# H04.net
KiCad netlist of a schematic drawn in EAGLE
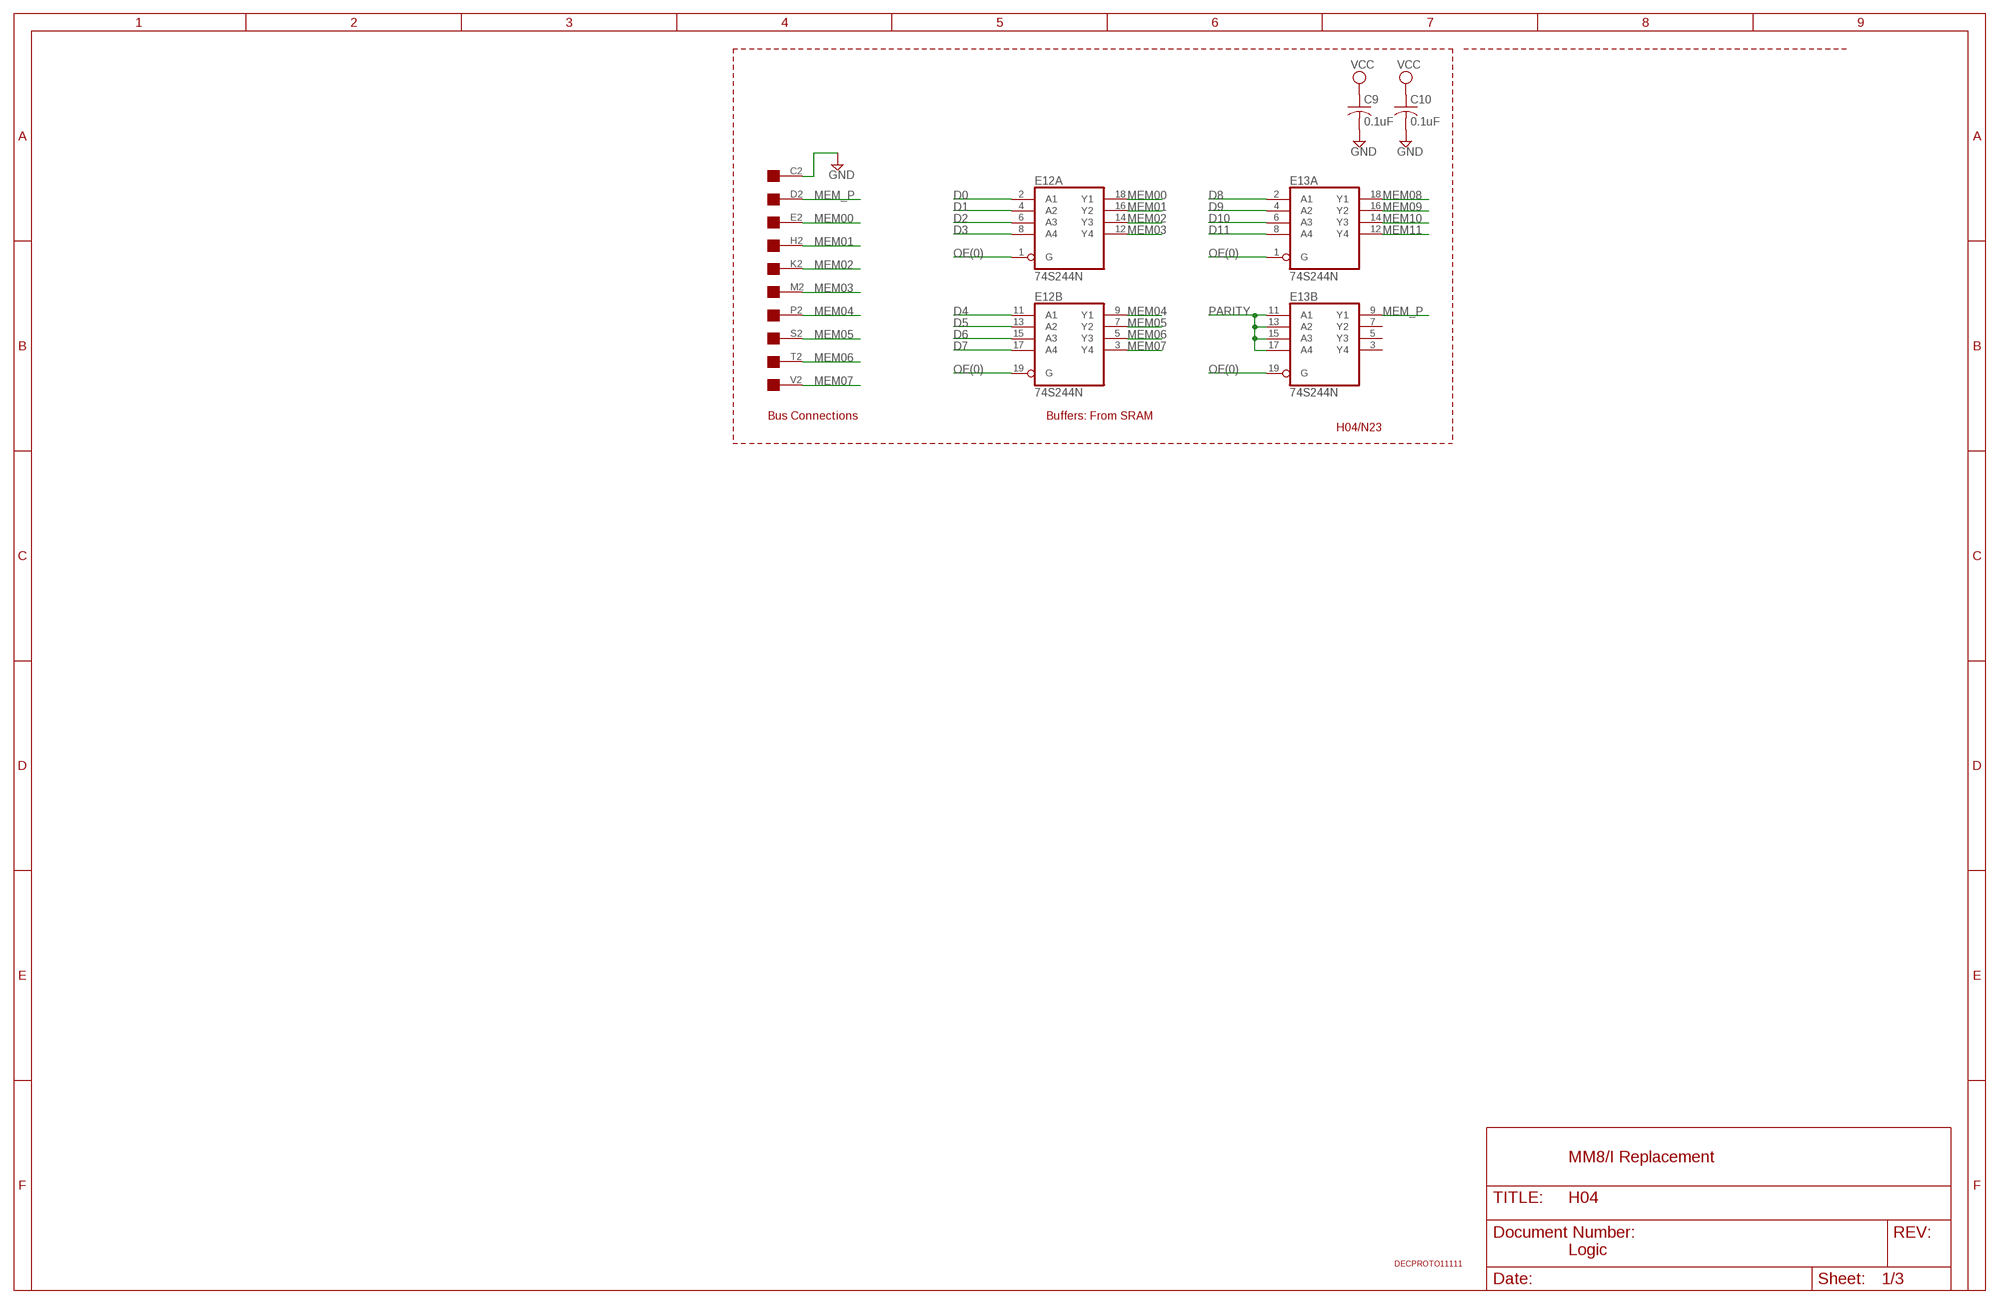
[diagram p0: schematic, sheet 1]
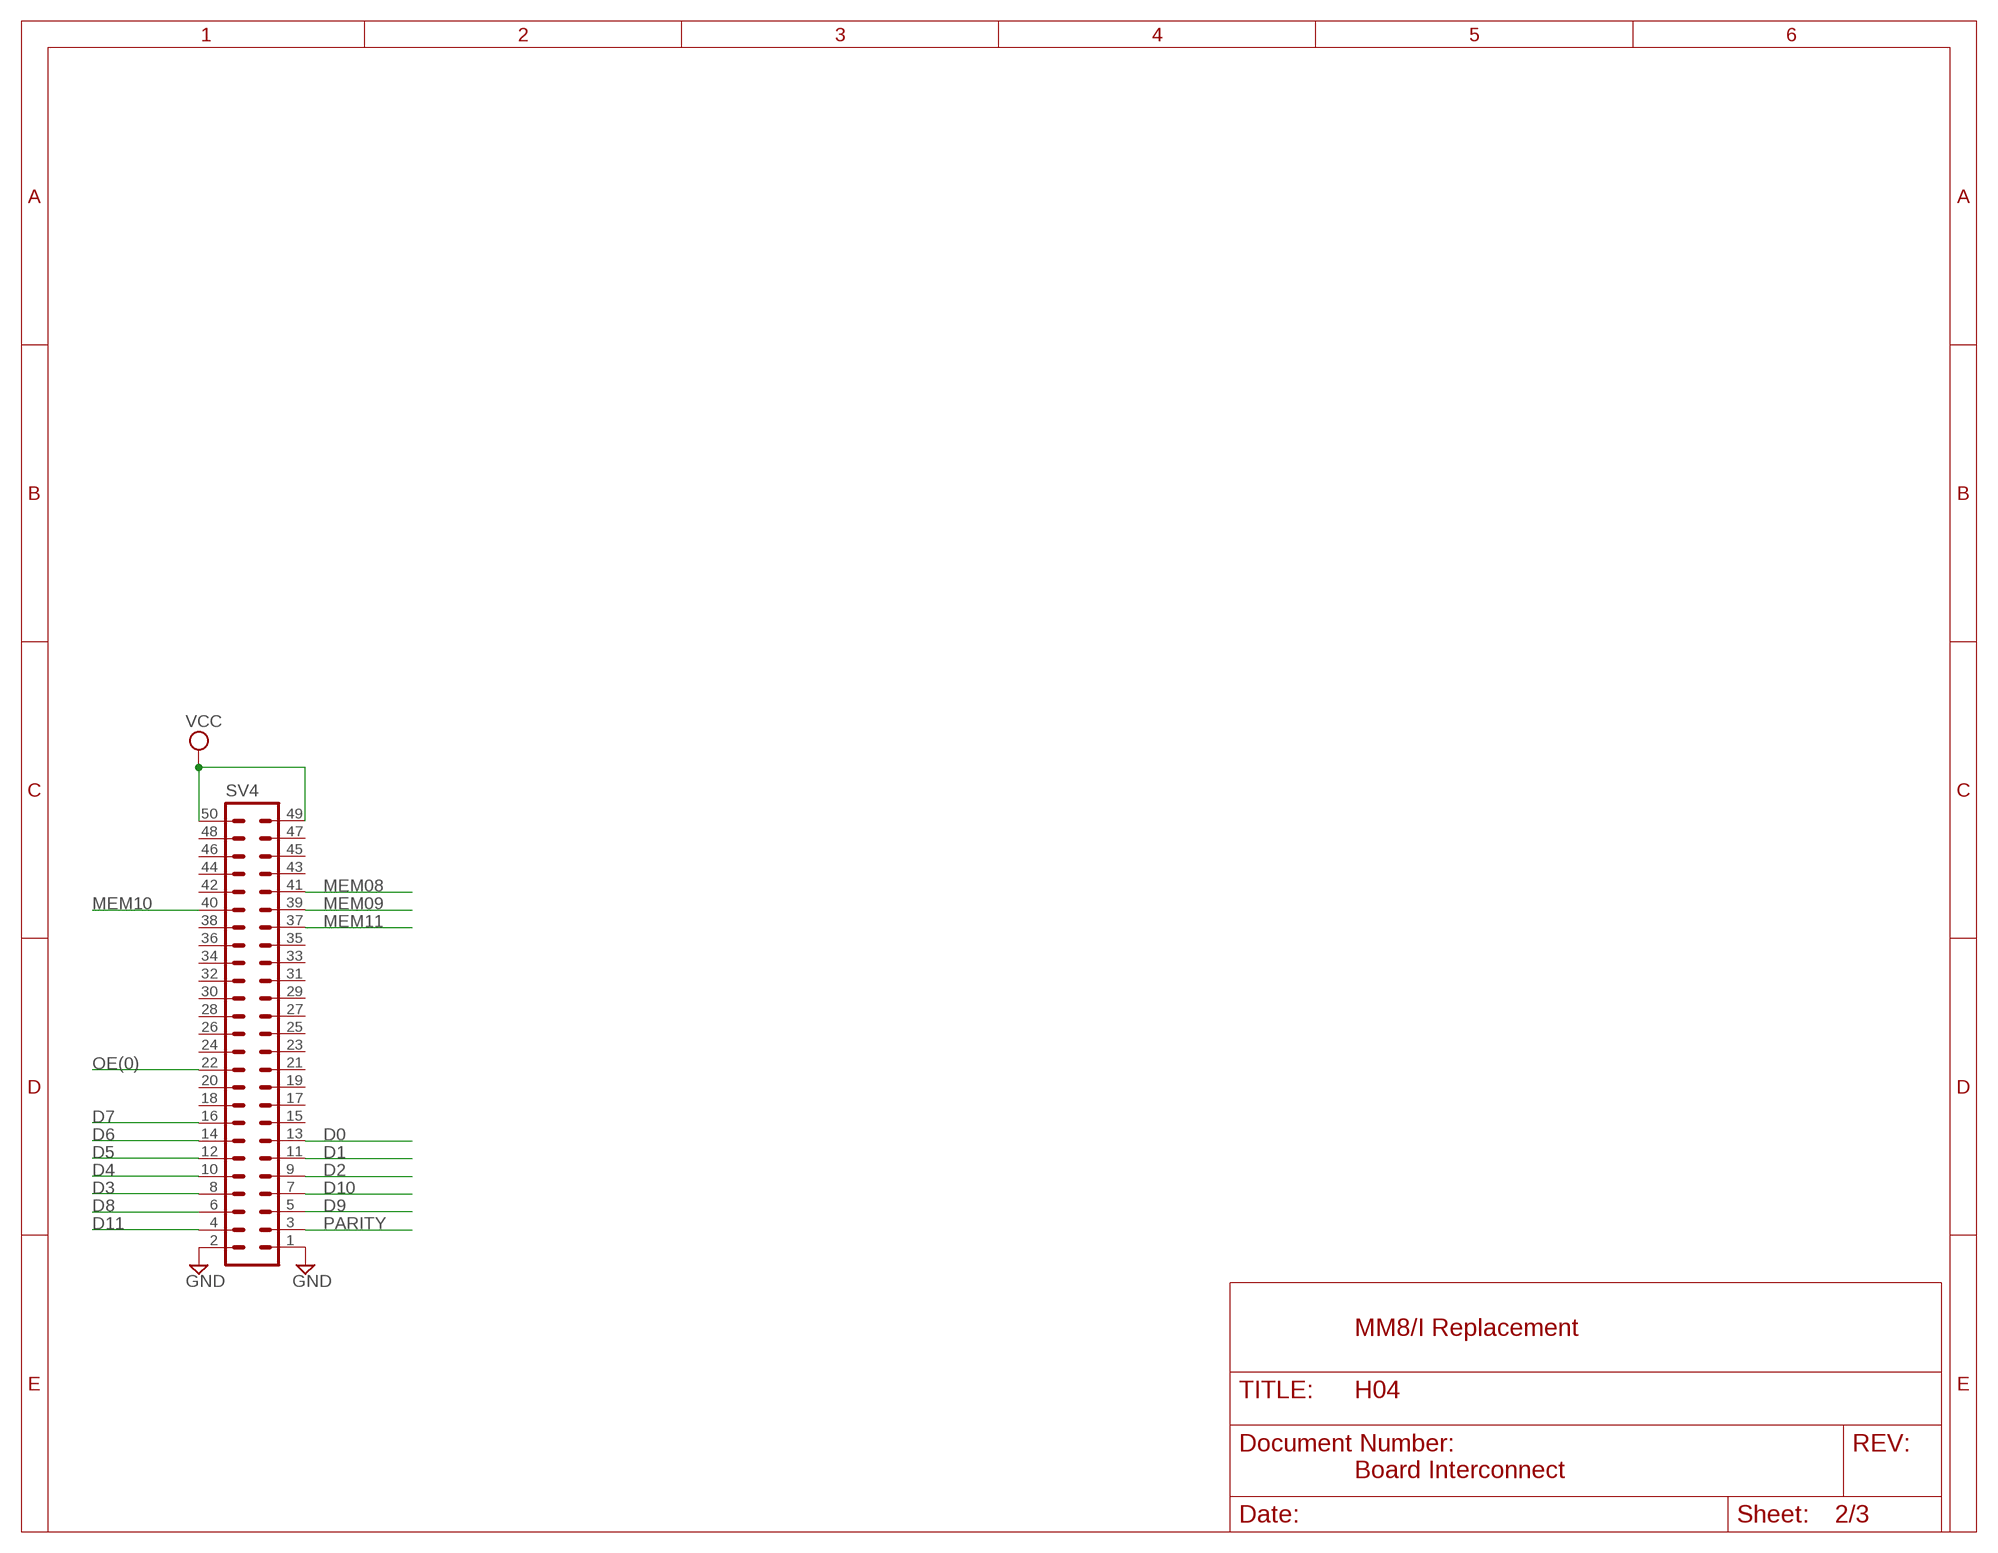
[diagram p1: schematic, sheet 2]
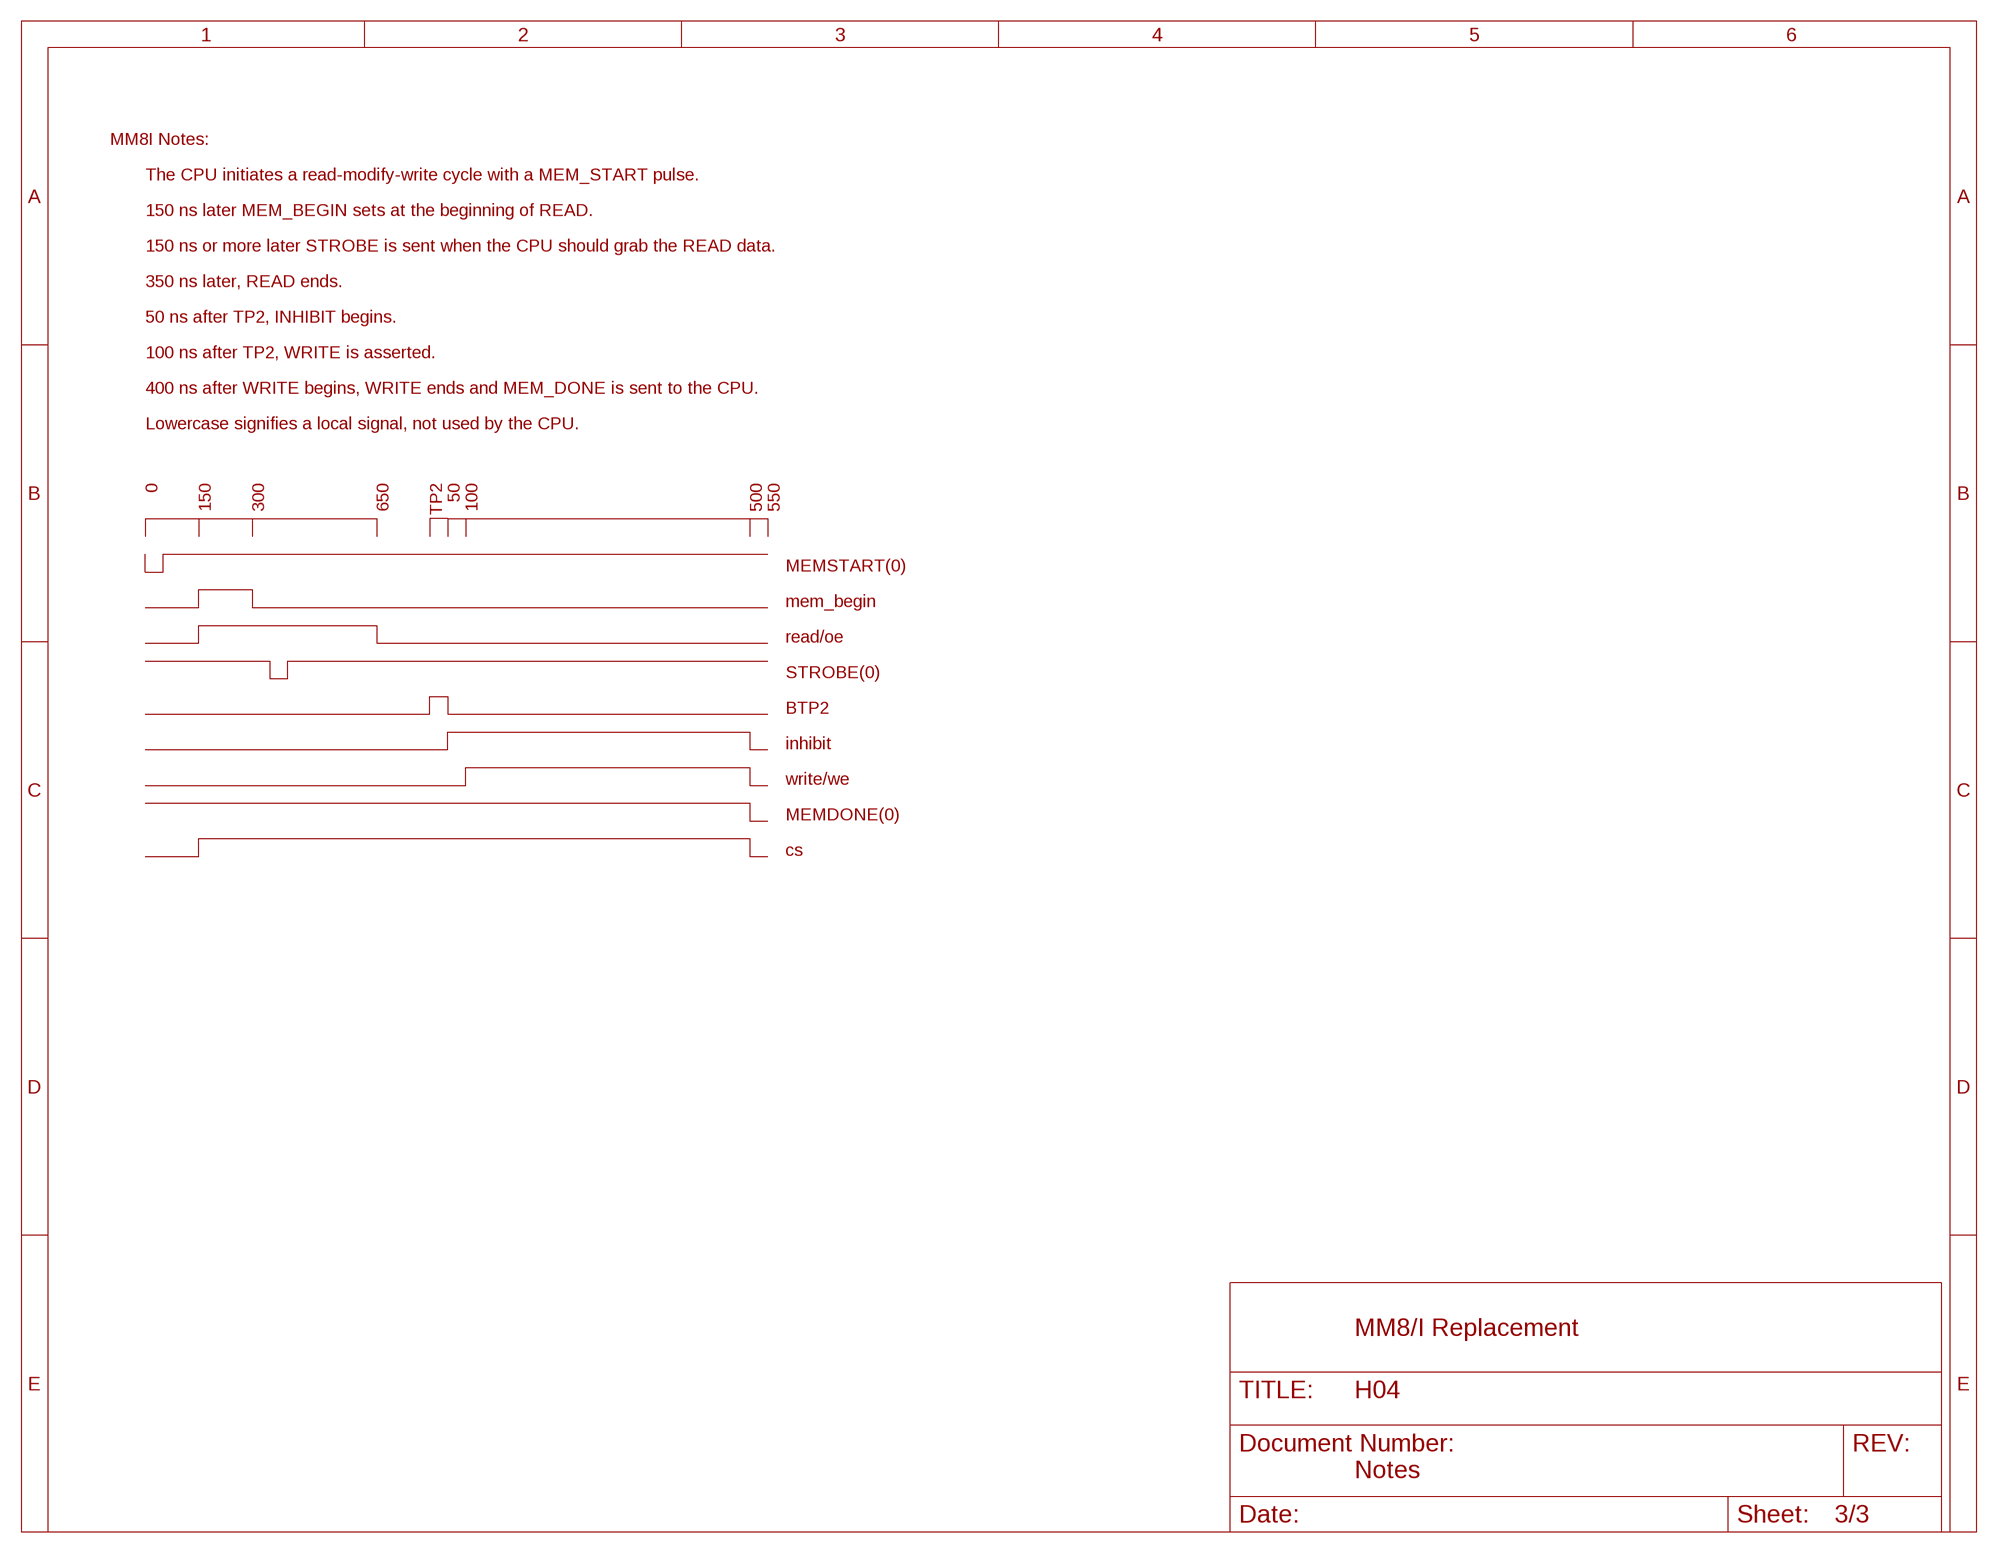
[diagram p2: schematic, sheet 3]

(export (version "E")
  (design (tool "Eeschema 10.0.6"))
  (components
    (comp (ref "SV4")
      (value "ML50L")
      (footprint "eagle-import:ML50L")
      (libsource (lib "eagle-import") (part "ML50L"))
    )
    (comp (ref "C9")
      (value "0.1uF")
      (footprint "eagle-import:C050-025X075")
      (libsource (lib "eagle-import") (part "C-US050-025X075"))
    )
    (comp (ref "C10")
      (value "0.1uF")
      (footprint "eagle-import:C050-025X075")
      (libsource (lib "eagle-import") (part "C-US050-025X075"))
    )
    (comp (ref "E12")
      (value "74S244N")
      (footprint "eagle-import:DIL20")
      (libsource (lib "eagle-import") (part "74244NS"))
    )
    (comp (ref "E13")
      (value "74S244N")
      (footprint "eagle-import:DIL20")
      (libsource (lib "eagle-import") (part "74244NS"))
    )
    (comp (ref "H04")
      (value "EDGE-1")
      (footprint "eagle-import:EDGE-CON1")
      (libsource (lib "eagle-import") (part "EDGE-1"))
    )
    (comp (ref "U$6")
      (value "DECPROTO11111")
      (footprint "eagle-import:DECPROTO11111")
      (libsource (lib "eagle-import") (part "DECPROTO11111"))
    )
  )
  (nets
    (net (code "1") (name "D0") (class "Default")
      (node (ref "E12") (pin "2") (pinfunction "A1_2") (pintype "input"))
      (node (ref "SV4") (pin "13") (pinfunction "13_13") (pintype "passive"))
    )
    (net (code "2") (name "D1") (class "Default")
      (node (ref "E12") (pin "4") (pinfunction "A2_4") (pintype "input"))
      (node (ref "SV4") (pin "11") (pinfunction "11_11") (pintype "passive"))
    )
    (net (code "3") (name "D2") (class "Default")
      (node (ref "E12") (pin "6") (pinfunction "A3_6") (pintype "input"))
      (node (ref "SV4") (pin "9") (pinfunction "9_9") (pintype "passive"))
    )
    (net (code "4") (name "D3") (class "Default")
      (node (ref "E12") (pin "8") (pinfunction "A4_8") (pintype "input"))
      (node (ref "SV4") (pin "8") (pinfunction "8_8") (pintype "passive"))
    )
    (net (code "5") (name "D4") (class "Default")
      (node (ref "E12") (pin "11") (pinfunction "A1_11") (pintype "input"))
      (node (ref "SV4") (pin "10") (pinfunction "10_10") (pintype "passive"))
    )
    (net (code "6") (name "D5") (class "Default")
      (node (ref "E12") (pin "13") (pinfunction "A2_13") (pintype "input"))
      (node (ref "SV4") (pin "12") (pinfunction "12_12") (pintype "passive"))
    )
    (net (code "7") (name "D6") (class "Default")
      (node (ref "E12") (pin "15") (pinfunction "A3_15") (pintype "input"))
      (node (ref "SV4") (pin "14") (pinfunction "14_14") (pintype "passive"))
    )
    (net (code "8") (name "D7") (class "Default")
      (node (ref "E12") (pin "17") (pinfunction "A4_17") (pintype "input"))
      (node (ref "SV4") (pin "16") (pinfunction "16_16") (pintype "passive"))
    )
    (net (code "9") (name "D8") (class "Default")
      (node (ref "E13") (pin "2") (pinfunction "A1_2") (pintype "input"))
      (node (ref "SV4") (pin "6") (pinfunction "6_6") (pintype "passive"))
    )
    (net (code "10") (name "D9") (class "Default")
      (node (ref "E13") (pin "4") (pinfunction "A2_4") (pintype "input"))
      (node (ref "SV4") (pin "5") (pinfunction "5_5") (pintype "passive"))
    )
    (net (code "11") (name "D10") (class "Default")
      (node (ref "E13") (pin "6") (pinfunction "A3_6") (pintype "input"))
      (node (ref "SV4") (pin "7") (pinfunction "7_7") (pintype "passive"))
    )
    (net (code "12") (name "D11") (class "Default")
      (node (ref "E13") (pin "8") (pinfunction "A4_8") (pintype "input"))
      (node (ref "SV4") (pin "4") (pinfunction "4_4") (pintype "passive"))
    )
    (net (code "13") (name "GND") (class "Default")
      (node (ref "C10") (pin "2") (pinfunction "2_2") (pintype "passive"))
      (node (ref "C9") (pin "2") (pinfunction "2_2") (pintype "passive"))
      (node (ref "H04") (pin "C2") (pinfunction "1_C2") (pintype "bidirectional"))
      (node (ref "SV4") (pin "1") (pinfunction "1_1") (pintype "passive"))
      (node (ref "SV4") (pin "2") (pinfunction "2_2") (pintype "passive"))
    )
    (net (code "14") (name "MEM00") (class "Default")
      (node (ref "E12") (pin "18") (pinfunction "Y1_18") (pintype "tri_state"))
      (node (ref "H04") (pin "E2") (pinfunction "1_E2") (pintype "bidirectional"))
    )
    (net (code "15") (name "MEM01") (class "Default")
      (node (ref "E12") (pin "16") (pinfunction "Y2_16") (pintype "tri_state"))
      (node (ref "H04") (pin "H2") (pinfunction "1_H2") (pintype "bidirectional"))
    )
    (net (code "16") (name "MEM02") (class "Default")
      (node (ref "E12") (pin "14") (pinfunction "Y3_14") (pintype "tri_state"))
      (node (ref "H04") (pin "K2") (pinfunction "1_K2") (pintype "bidirectional"))
    )
    (net (code "17") (name "MEM03") (class "Default")
      (node (ref "E12") (pin "12") (pinfunction "Y4_12") (pintype "tri_state"))
      (node (ref "H04") (pin "M2") (pinfunction "1_M2") (pintype "bidirectional"))
    )
    (net (code "18") (name "MEM04") (class "Default")
      (node (ref "E12") (pin "9") (pinfunction "Y1_9") (pintype "tri_state"))
      (node (ref "H04") (pin "P2") (pinfunction "1_P2") (pintype "bidirectional"))
    )
    (net (code "19") (name "MEM05") (class "Default")
      (node (ref "E12") (pin "7") (pinfunction "Y2_7") (pintype "tri_state"))
      (node (ref "H04") (pin "S2") (pinfunction "1_S2") (pintype "bidirectional"))
    )
    (net (code "20") (name "MEM06") (class "Default")
      (node (ref "E12") (pin "5") (pinfunction "Y3_5") (pintype "tri_state"))
      (node (ref "H04") (pin "T2") (pinfunction "1_T2") (pintype "bidirectional"))
    )
    (net (code "21") (name "MEM07") (class "Default")
      (node (ref "E12") (pin "3") (pinfunction "Y4_3") (pintype "tri_state"))
      (node (ref "H04") (pin "V2") (pinfunction "1_V2") (pintype "bidirectional"))
    )
    (net (code "22") (name "MEM08") (class "Default")
      (node (ref "E13") (pin "18") (pinfunction "Y1_18") (pintype "tri_state"))
      (node (ref "SV4") (pin "41") (pinfunction "41_41") (pintype "passive"))
    )
    (net (code "23") (name "MEM09") (class "Default")
      (node (ref "E13") (pin "16") (pinfunction "Y2_16") (pintype "tri_state"))
      (node (ref "SV4") (pin "39") (pinfunction "39_39") (pintype "passive"))
    )
    (net (code "24") (name "MEM10") (class "Default")
      (node (ref "E13") (pin "14") (pinfunction "Y3_14") (pintype "tri_state"))
      (node (ref "SV4") (pin "40") (pinfunction "40_40") (pintype "passive"))
    )
    (net (code "25") (name "MEM11") (class "Default")
      (node (ref "E13") (pin "12") (pinfunction "Y4_12") (pintype "tri_state"))
      (node (ref "SV4") (pin "37") (pinfunction "37_37") (pintype "passive"))
    )
    (net (code "26") (name "MEM_P") (class "Default")
      (node (ref "E13") (pin "9") (pinfunction "Y1_9") (pintype "tri_state"))
      (node (ref "H04") (pin "D2") (pinfunction "1_D2") (pintype "bidirectional"))
    )
    (net (code "27") (name "OE(0)") (class "Default")
      (node (ref "E12") (pin "1") (pinfunction "G_1") (pintype "input"))
      (node (ref "E12") (pin "19") (pinfunction "G_19") (pintype "input"))
      (node (ref "E13") (pin "1") (pinfunction "G_1") (pintype "input"))
      (node (ref "E13") (pin "19") (pinfunction "G_19") (pintype "input"))
      (node (ref "SV4") (pin "22") (pinfunction "22_22") (pintype "passive"))
    )
    (net (code "28") (name "PARITY") (class "Default")
      (node (ref "E13") (pin "11") (pinfunction "A1_11") (pintype "input"))
      (node (ref "E13") (pin "13") (pinfunction "A2_13") (pintype "input"))
      (node (ref "E13") (pin "15") (pinfunction "A3_15") (pintype "input"))
      (node (ref "E13") (pin "17") (pinfunction "A4_17") (pintype "input"))
      (node (ref "SV4") (pin "3") (pinfunction "3_3") (pintype "passive"))
    )
    (net (code "29") (name "VCC") (class "Default")
      (node (ref "C10") (pin "1") (pinfunction "1_1") (pintype "passive"))
      (node (ref "C9") (pin "1") (pinfunction "1_1") (pintype "passive"))
      (node (ref "SV4") (pin "49") (pinfunction "49_49") (pintype "passive"))
      (node (ref "SV4") (pin "50") (pinfunction "50_50") (pintype "passive"))
    )
    (net (code "30") (name "unconnected-(E13B-Y2-Pad7)") (class "Default")
      (node (ref "E13") (pin "7") (pinfunction "Y2_7") (pintype "tri_state"))
    )
    (net (code "31") (name "unconnected-(E13B-Y3-Pad5)") (class "Default")
      (node (ref "E13") (pin "5") (pinfunction "Y3_5") (pintype "tri_state"))
    )
    (net (code "32") (name "unconnected-(E13B-Y4-Pad3)") (class "Default")
      (node (ref "E13") (pin "3") (pinfunction "Y4_3") (pintype "tri_state"))
    )
    (net (code "33") (name "unconnected-(SV4-Pad15)") (class "Default")
      (node (ref "SV4") (pin "15") (pinfunction "15_15") (pintype "passive"))
    )
    (net (code "34") (name "unconnected-(SV4-Pad17)") (class "Default")
      (node (ref "SV4") (pin "17") (pinfunction "17_17") (pintype "passive"))
    )
    (net (code "35") (name "unconnected-(SV4-Pad18)") (class "Default")
      (node (ref "SV4") (pin "18") (pinfunction "18_18") (pintype "passive"))
    )
    (net (code "36") (name "unconnected-(SV4-Pad19)") (class "Default")
      (node (ref "SV4") (pin "19") (pinfunction "19_19") (pintype "passive"))
    )
    (net (code "37") (name "unconnected-(SV4-Pad20)") (class "Default")
      (node (ref "SV4") (pin "20") (pinfunction "20_20") (pintype "passive"))
    )
    (net (code "38") (name "unconnected-(SV4-Pad21)") (class "Default")
      (node (ref "SV4") (pin "21") (pinfunction "21_21") (pintype "passive"))
    )
    (net (code "39") (name "unconnected-(SV4-Pad23)") (class "Default")
      (node (ref "SV4") (pin "23") (pinfunction "23_23") (pintype "passive"))
    )
    (net (code "40") (name "unconnected-(SV4-Pad24)") (class "Default")
      (node (ref "SV4") (pin "24") (pinfunction "24_24") (pintype "passive"))
    )
    (net (code "41") (name "unconnected-(SV4-Pad25)") (class "Default")
      (node (ref "SV4") (pin "25") (pinfunction "25_25") (pintype "passive"))
    )
    (net (code "42") (name "unconnected-(SV4-Pad26)") (class "Default")
      (node (ref "SV4") (pin "26") (pinfunction "26_26") (pintype "passive"))
    )
    (net (code "43") (name "unconnected-(SV4-Pad27)") (class "Default")
      (node (ref "SV4") (pin "27") (pinfunction "27_27") (pintype "passive"))
    )
    (net (code "44") (name "unconnected-(SV4-Pad28)") (class "Default")
      (node (ref "SV4") (pin "28") (pinfunction "28_28") (pintype "passive"))
    )
    (net (code "45") (name "unconnected-(SV4-Pad29)") (class "Default")
      (node (ref "SV4") (pin "29") (pinfunction "29_29") (pintype "passive"))
    )
    (net (code "46") (name "unconnected-(SV4-Pad30)") (class "Default")
      (node (ref "SV4") (pin "30") (pinfunction "30_30") (pintype "passive"))
    )
    (net (code "47") (name "unconnected-(SV4-Pad31)") (class "Default")
      (node (ref "SV4") (pin "31") (pinfunction "31_31") (pintype "passive"))
    )
    (net (code "48") (name "unconnected-(SV4-Pad32)") (class "Default")
      (node (ref "SV4") (pin "32") (pinfunction "32_32") (pintype "passive"))
    )
    (net (code "49") (name "unconnected-(SV4-Pad33)") (class "Default")
      (node (ref "SV4") (pin "33") (pinfunction "33_33") (pintype "passive"))
    )
    (net (code "50") (name "unconnected-(SV4-Pad34)") (class "Default")
      (node (ref "SV4") (pin "34") (pinfunction "34_34") (pintype "passive"))
    )
    (net (code "51") (name "unconnected-(SV4-Pad35)") (class "Default")
      (node (ref "SV4") (pin "35") (pinfunction "35_35") (pintype "passive"))
    )
    (net (code "52") (name "unconnected-(SV4-Pad36)") (class "Default")
      (node (ref "SV4") (pin "36") (pinfunction "36_36") (pintype "passive"))
    )
    (net (code "53") (name "unconnected-(SV4-Pad38)") (class "Default")
      (node (ref "SV4") (pin "38") (pinfunction "38_38") (pintype "passive"))
    )
    (net (code "54") (name "unconnected-(SV4-Pad42)") (class "Default")
      (node (ref "SV4") (pin "42") (pinfunction "42_42") (pintype "passive"))
    )
    (net (code "55") (name "unconnected-(SV4-Pad43)") (class "Default")
      (node (ref "SV4") (pin "43") (pinfunction "43_43") (pintype "passive"))
    )
    (net (code "56") (name "unconnected-(SV4-Pad44)") (class "Default")
      (node (ref "SV4") (pin "44") (pinfunction "44_44") (pintype "passive"))
    )
    (net (code "57") (name "unconnected-(SV4-Pad45)") (class "Default")
      (node (ref "SV4") (pin "45") (pinfunction "45_45") (pintype "passive"))
    )
    (net (code "58") (name "unconnected-(SV4-Pad46)") (class "Default")
      (node (ref "SV4") (pin "46") (pinfunction "46_46") (pintype "passive"))
    )
    (net (code "59") (name "unconnected-(SV4-Pad47)") (class "Default")
      (node (ref "SV4") (pin "47") (pinfunction "47_47") (pintype "passive"))
    )
    (net (code "60") (name "unconnected-(SV4-Pad48)") (class "Default")
      (node (ref "SV4") (pin "48") (pinfunction "48_48") (pintype "passive"))
    )
  )
)
